# design.net
KiCad netlist of a schematic drawn in Altium Designer
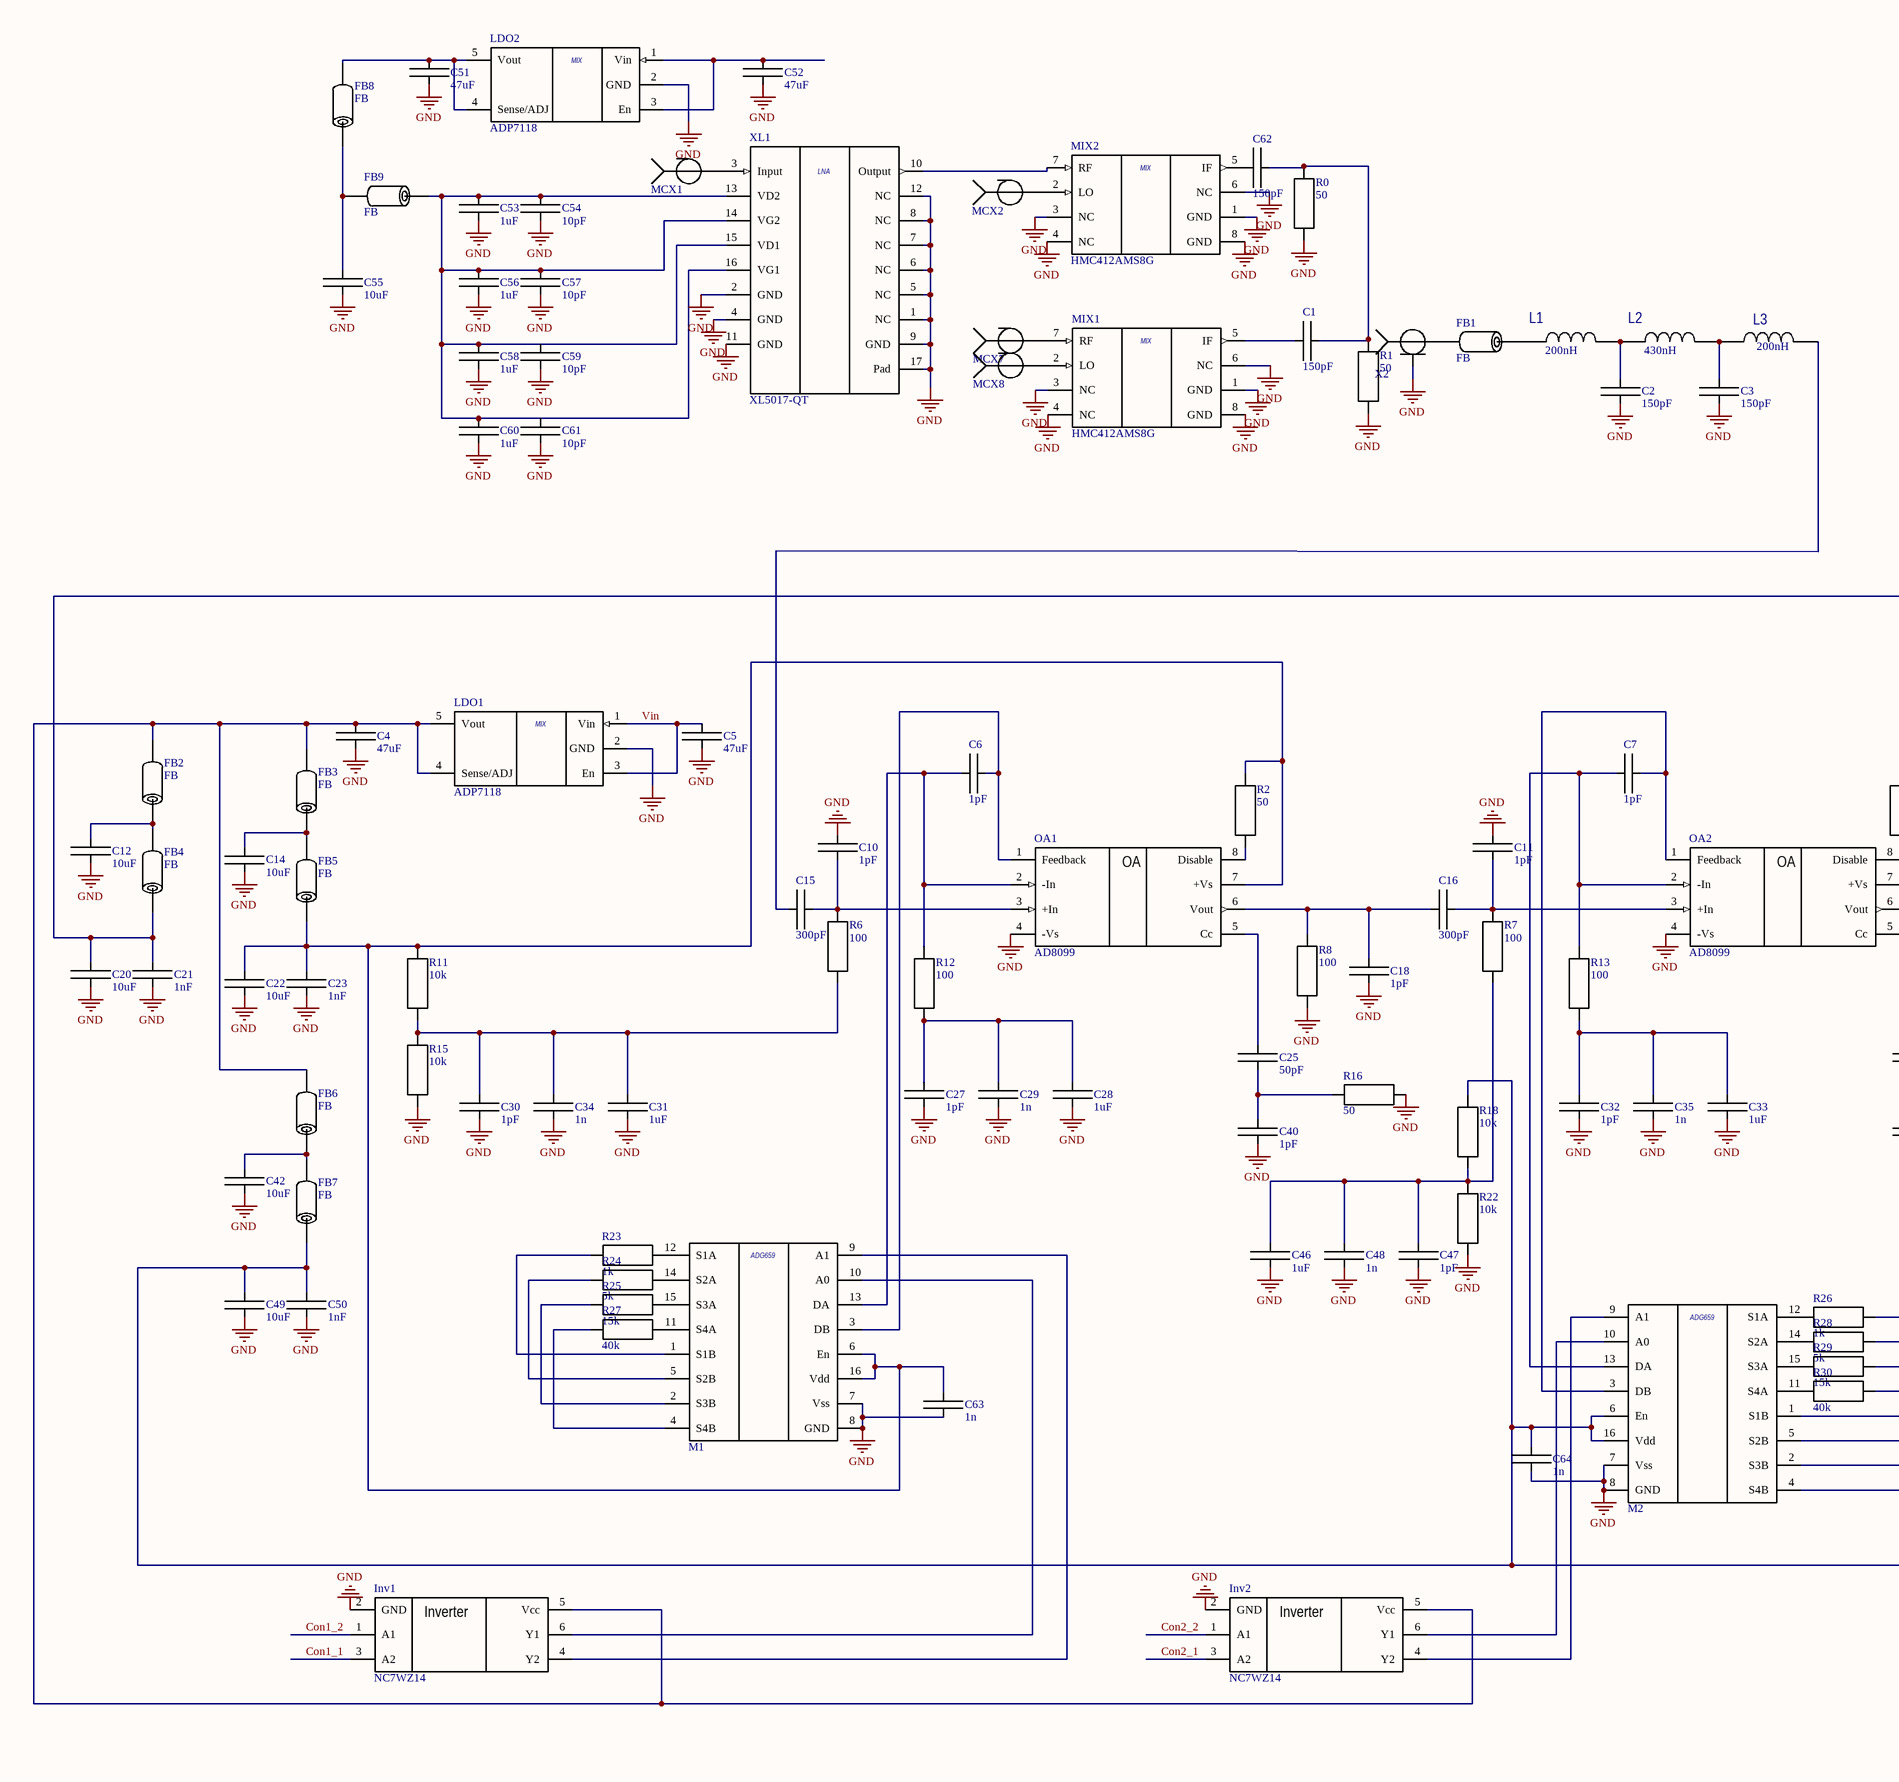
[diagram p0: Приемник.SchDoc, left]
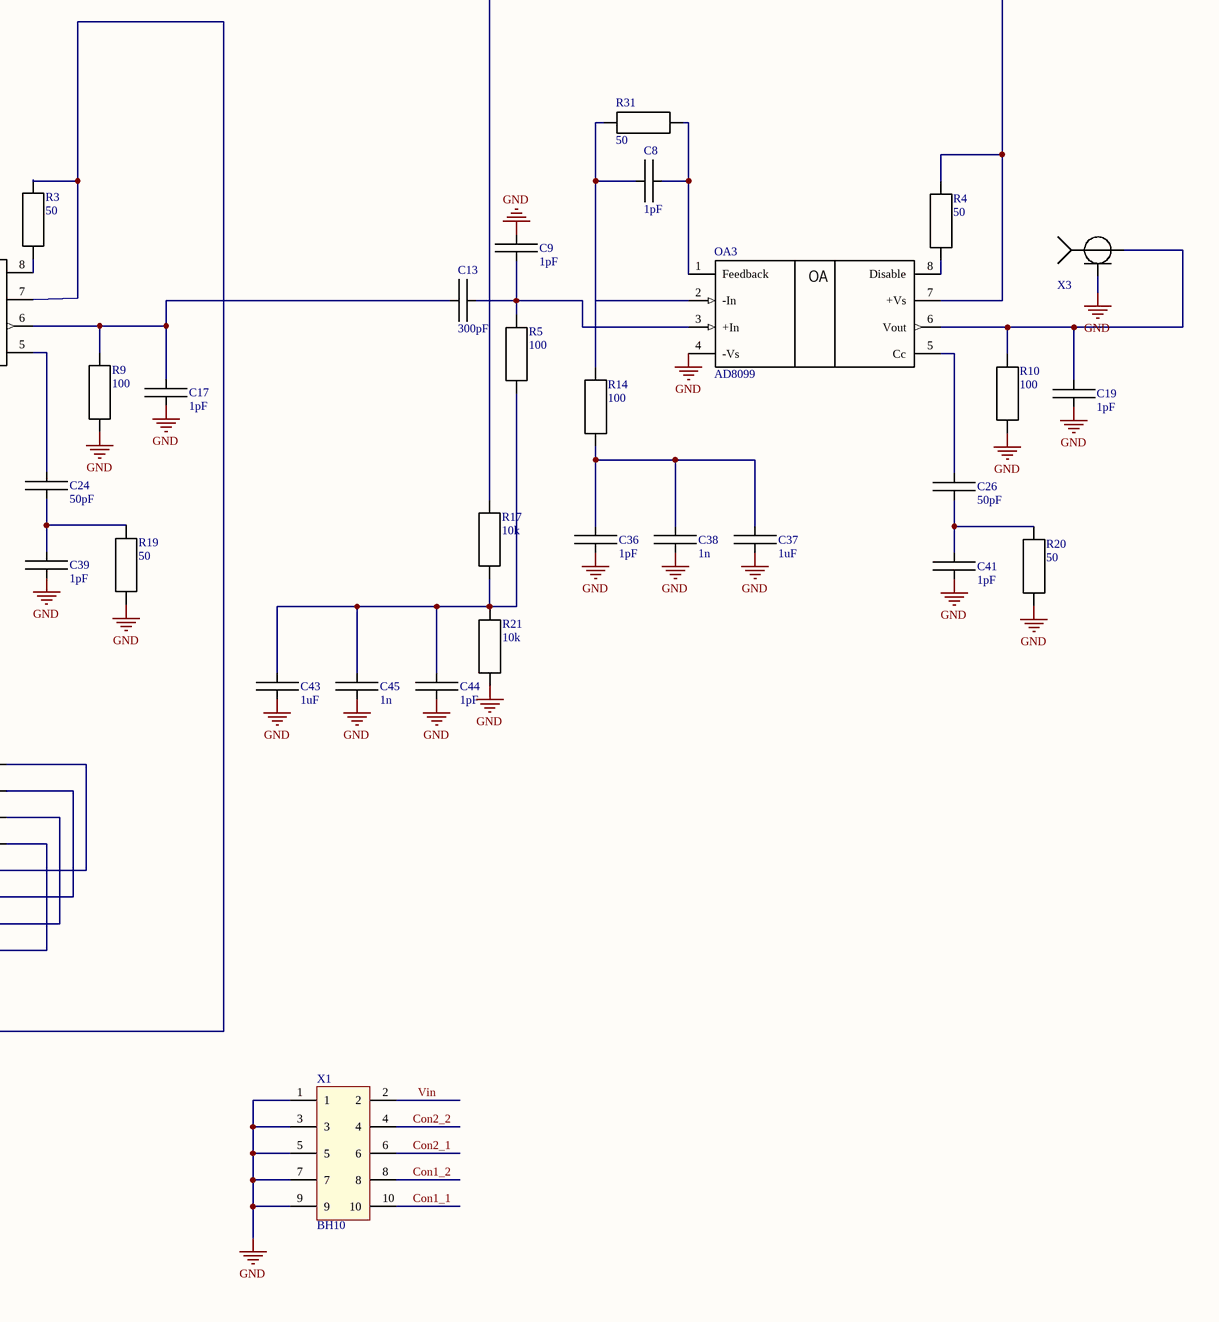
[diagram p1: Приемник.SchDoc, right]

(export (version "E")
  (design (tool "Eeschema 10.0.6"))
  (components
    (comp (ref "C1") (value "150pF") (footprint "SMD0402") (libsource (lib "My_Library") (part "CAP0402")))
    (comp (ref "C2") (value "150pF") (footprint "SMD0402") (libsource (lib "My_Library") (part "CAP0402")))
    (comp (ref "C3") (value "150pF") (footprint "SMD0402") (libsource (lib "My_Library") (part "CAP0402")))
    (comp (ref "C4")
      (value "47uF")
      (footprint "B3528-21")
      (libsource (lib "My_Library") (part "CAPT10V4.7-100uF"))
    )
    (comp (ref "C5")
      (value "47uF")
      (footprint "B3528-21")
      (libsource (lib "My_Library") (part "CAPT10V4.7-100uF"))
    )
    (comp (ref "C6") (value "1pF") (footprint "SMD0402") (libsource (lib "My_Library") (part "CAP0402")))
    (comp (ref "C7") (value "1pF") (footprint "SMD0402") (libsource (lib "My_Library") (part "CAP0402")))
    (comp (ref "C8") (value "1pF") (footprint "SMD0402") (libsource (lib "My_Library") (part "CAP0402")))
    (comp (ref "C9") (value "1pF") (footprint "SMD0402") (libsource (lib "My_Library") (part "CAP0402")))
    (comp (ref "C10") (value "1pF") (footprint "SMD0402") (libsource (lib "My_Library") (part "CAP0402")))
    (comp (ref "C11") (value "1pF") (footprint "SMD0402") (libsource (lib "My_Library") (part "CAP0402")))
    (comp (ref "C12") (value "10uF") (footprint "SMD0603") (libsource (lib "My_Library") (part "CAP0603")))
    (comp (ref "C13") (value "300pF") (footprint "SMD0402") (libsource (lib "My_Library") (part "CAP0402")))
    (comp (ref "C14") (value "10uF") (footprint "SMD0603") (libsource (lib "My_Library") (part "CAP0603")))
    (comp (ref "C15") (value "300pF") (footprint "SMD0402") (libsource (lib "My_Library") (part "CAP0402")))
    (comp (ref "C16") (value "300pF") (footprint "SMD0402") (libsource (lib "My_Library") (part "CAP0402")))
    (comp (ref "C17") (value "1pF") (footprint "SMD0402") (libsource (lib "My_Library") (part "CAP0402")))
    (comp (ref "C18") (value "1pF") (footprint "SMD0402") (libsource (lib "My_Library") (part "CAP0402")))
    (comp (ref "C19") (value "1pF") (footprint "SMD0402") (libsource (lib "My_Library") (part "CAP0402")))
    (comp (ref "C20") (value "10uF") (footprint "SMD0603") (libsource (lib "My_Library") (part "CAP0603")))
    (comp (ref "C21") (value "1nF") (footprint "SMD0402") (libsource (lib "My_Library") (part "CAP0402")))
    (comp (ref "C22") (value "10uF") (footprint "SMD0603") (libsource (lib "My_Library") (part "CAP0603")))
    (comp (ref "C23") (value "1nF") (footprint "SMD0402") (libsource (lib "My_Library") (part "CAP0402")))
    (comp (ref "C24") (value "50pF") (footprint "SMD0402") (libsource (lib "My_Library") (part "CAP0402")))
    (comp (ref "C25") (value "50pF") (footprint "SMD0402") (libsource (lib "My_Library") (part "CAP0402")))
    (comp (ref "C26") (value "50pF") (footprint "SMD0402") (libsource (lib "My_Library") (part "CAP0402")))
    (comp (ref "C27") (value "1pF") (footprint "SMD0402") (libsource (lib "My_Library") (part "CAP0402")))
    (comp (ref "C28") (value "1uF") (footprint "SMD0603") (libsource (lib "My_Library") (part "CAP0603")))
    (comp (ref "C29") (value "1n") (footprint "SMD0402") (libsource (lib "My_Library") (part "CAP0402")))
    (comp (ref "C30") (value "1pF") (footprint "SMD0402") (libsource (lib "My_Library") (part "CAP0402")))
    (comp (ref "C31") (value "1uF") (footprint "SMD0603") (libsource (lib "My_Library") (part "CAP0603")))
    (comp (ref "C32") (value "1pF") (footprint "SMD0402") (libsource (lib "My_Library") (part "CAP0402")))
    (comp (ref "C33") (value "1uF") (footprint "SMD0603") (libsource (lib "My_Library") (part "CAP0603")))
    (comp (ref "C34") (value "1n") (footprint "SMD0402") (libsource (lib "My_Library") (part "CAP0402")))
    (comp (ref "C35") (value "1n") (footprint "SMD0402") (libsource (lib "My_Library") (part "CAP0402")))
    (comp (ref "C36") (value "1pF") (footprint "SMD0402") (libsource (lib "My_Library") (part "CAP0402")))
    (comp (ref "C37") (value "1uF") (footprint "SMD0603") (libsource (lib "My_Library") (part "CAP0603")))
    (comp (ref "C38") (value "1n") (footprint "SMD0402") (libsource (lib "My_Library") (part "CAP0402")))
    (comp (ref "C39") (value "1pF") (footprint "SMD0402") (libsource (lib "My_Library") (part "CAP0402")))
    (comp (ref "C40") (value "1pF") (footprint "SMD0402") (libsource (lib "My_Library") (part "CAP0402")))
    (comp (ref "C41") (value "1pF") (footprint "SMD0402") (libsource (lib "My_Library") (part "CAP0402")))
    (comp (ref "C42") (value "10uF") (footprint "SMD0603") (libsource (lib "My_Library") (part "CAP0603")))
    (comp (ref "C43") (value "1uF") (footprint "SMD0603") (libsource (lib "My_Library") (part "CAP0603")))
    (comp (ref "C44") (value "1pF") (footprint "SMD0402") (libsource (lib "My_Library") (part "CAP0402")))
    (comp (ref "C45") (value "1n") (footprint "SMD0402") (libsource (lib "My_Library") (part "CAP0402")))
    (comp (ref "C46") (value "1uF") (footprint "SMD0603") (libsource (lib "My_Library") (part "CAP0603")))
    (comp (ref "C47") (value "1pF") (footprint "SMD0402") (libsource (lib "My_Library") (part "CAP0402")))
    (comp (ref "C48") (value "1n") (footprint "SMD0402") (libsource (lib "My_Library") (part "CAP0402")))
    (comp (ref "C49") (value "10uF") (footprint "SMD0603") (libsource (lib "My_Library") (part "CAP0603")))
    (comp (ref "C50") (value "1nF") (footprint "SMD0402") (libsource (lib "My_Library") (part "CAP0402")))
    (comp (ref "C51")
      (value "47uF")
      (footprint "B3528-21")
      (libsource (lib "My_Library") (part "CAPT10V4.7-100uF"))
    )
    (comp (ref "C52")
      (value "47uF")
      (footprint "B3528-21")
      (libsource (lib "My_Library") (part "CAPT10V4.7-100uF"))
    )
    (comp (ref "C53") (value "1uF") (footprint "SMD0603") (libsource (lib "My_Library") (part "CAP0603")))
    (comp (ref "C54") (value "10pF") (footprint "SMD0402") (libsource (lib "My_Library") (part "CAP0402")))
    (comp (ref "C55") (value "10uF") (footprint "SMD0603") (libsource (lib "My_Library") (part "CAP0603")))
    (comp (ref "C56") (value "1uF") (footprint "SMD0603") (libsource (lib "My_Library") (part "CAP0603")))
    (comp (ref "C57") (value "10pF") (footprint "SMD0402") (libsource (lib "My_Library") (part "CAP0402")))
    (comp (ref "C58") (value "1uF") (footprint "SMD0603") (libsource (lib "My_Library") (part "CAP0603")))
    (comp (ref "C59") (value "10pF") (footprint "SMD0402") (libsource (lib "My_Library") (part "CAP0402")))
    (comp (ref "C60") (value "1uF") (footprint "SMD0603") (libsource (lib "My_Library") (part "CAP0603")))
    (comp (ref "C61") (value "10pF") (footprint "SMD0402") (libsource (lib "My_Library") (part "CAP0402")))
    (comp (ref "C62") (value "150pF") (footprint "SMD0402") (libsource (lib "My_Library") (part "CAP0402")))
    (comp (ref "C63") (value "1n") (footprint "SMD0402") (libsource (lib "My_Library") (part "CAP0402")))
    (comp (ref "C64") (value "1n") (footprint "SMD0402") (libsource (lib "My_Library") (part "CAP0402")))
    (comp (ref "FB1") (value "FB") (footprint "FV1206") (libsource (lib "") (part "FB_1")))
    (comp (ref "FB2") (value "FB") (footprint "FV1206") (libsource (lib "My_Library") (part "FB")))
    (comp (ref "FB3") (value "FB") (footprint "FV1206") (libsource (lib "My_Library") (part "FB")))
    (comp (ref "FB4") (value "FB") (footprint "FV1206") (libsource (lib "My_Library") (part "FB")))
    (comp (ref "FB5") (value "FB") (footprint "FV1206") (libsource (lib "My_Library") (part "FB")))
    (comp (ref "FB6") (value "FB") (footprint "FV1206") (libsource (lib "My_Library") (part "FB")))
    (comp (ref "FB7") (value "FB") (footprint "FV1206") (libsource (lib "My_Library") (part "FB")))
    (comp (ref "FB8") (value "FB") (footprint "FV1206") (libsource (lib "My_Library") (part "FB")))
    (comp (ref "FB9") (value "FB") (footprint "FV1206") (libsource (lib "") (part "FB_1")))
    (comp (ref "Inv1") (value "NC7WZ14") (footprint "SC70") (libsource (lib "My_Library") (part "NC7WZ14")))
    (comp (ref "Inv2") (value "NC7WZ14") (footprint "SC70") (libsource (lib "My_Library") (part "NC7WZ14")))
    (comp (ref "L1") (value "200nH") (footprint "SMD0603") (libsource (lib "My_Library") (part "IND0603")))
    (comp (ref "L2") (value "430nH") (footprint "SMD0603") (libsource (lib "My_Library") (part "IND0603")))
    (comp (ref "L3") (value "200nH") (footprint "SMD0603") (libsource (lib "My_Library") (part "IND0603")))
    (comp (ref "LDO1") (value "ADP7118") (footprint "TSOT5") (libsource (lib "My_Library") (part "ADP7118")))
    (comp (ref "LDO2") (value "ADP7118") (footprint "TSOT5") (libsource (lib "My_Library") (part "ADP7118")))
    (comp (ref "M1")
      (value "ADG658_659")
      (footprint "TSSOP16")
      (libsource (lib "My_Library") (part "ADG658_659"))
    )
    (comp (ref "M2")
      (value "ADG658_659")
      (footprint "TSSOP16")
      (libsource (lib "My_Library") (part "ADG658_659"))
    )
    (comp (ref "MCX1") (value "MCX") (footprint "MCX") (libsource (lib "My_Library") (part "MCX")))
    (comp (ref "MCX2") (value "MCX") (footprint "MCX") (libsource (lib "My_Library") (part "MCX")))
    (comp (ref "MCX7") (value "MCX") (footprint "MCX") (libsource (lib "My_Library") (part "MCX")))
    (comp (ref "MCX8") (value "MCX") (footprint "MCX") (libsource (lib "My_Library") (part "MCX")))
    (comp (ref "MIX1")
      (value "HMC412AMS8G")
      (footprint "HMC412AMS8G")
      (libsource (lib "My_Library") (part "HMC412AMS8G"))
    )
    (comp (ref "MIX2")
      (value "HMC412AMS8G")
      (footprint "HMC412AMS8G")
      (libsource (lib "My_Library") (part "HMC412AMS8G"))
    )
    (comp (ref "OA1") (value "AD8099") (footprint "SOIC_8_EP") (libsource (lib "My_Library") (part "AD8099")))
    (comp (ref "OA2") (value "AD8099") (footprint "SOIC_8_EP") (libsource (lib "My_Library") (part "AD8099")))
    (comp (ref "OA3") (value "AD8099") (footprint "SOIC_8_EP") (libsource (lib "My_Library") (part "AD8099")))
    (comp (ref "R0") (value "50") (footprint "SMD0603") (libsource (lib "My_Library") (part "RES0402")))
    (comp (ref "R1") (value "50") (footprint "SMD0603") (libsource (lib "My_Library") (part "RES0402")))
    (comp (ref "R2") (value "50") (footprint "SMD0603") (libsource (lib "My_Library") (part "RES0402")))
    (comp (ref "R3") (value "50") (footprint "SMD0603") (libsource (lib "My_Library") (part "RES0402")))
    (comp (ref "R4") (value "50") (footprint "SMD0603") (libsource (lib "My_Library") (part "RES0402")))
    (comp (ref "R5") (value "100") (footprint "SMD0603") (libsource (lib "My_Library") (part "RES0402")))
    (comp (ref "R6") (value "100") (footprint "SMD0603") (libsource (lib "My_Library") (part "RES0402")))
    (comp (ref "R7") (value "100") (footprint "SMD0603") (libsource (lib "My_Library") (part "RES0402")))
    (comp (ref "R8") (value "100") (footprint "SMD0603") (libsource (lib "My_Library") (part "RES0402")))
    (comp (ref "R9") (value "100") (footprint "SMD0603") (libsource (lib "My_Library") (part "RES0402")))
    (comp (ref "R10") (value "100") (footprint "SMD0603") (libsource (lib "My_Library") (part "RES0402")))
    (comp (ref "R11") (value "10k") (footprint "SMD0603") (libsource (lib "My_Library") (part "RES0402")))
    (comp (ref "R12") (value "100") (footprint "SMD0603") (libsource (lib "My_Library") (part "RES0402")))
    (comp (ref "R13") (value "100") (footprint "SMD0603") (libsource (lib "My_Library") (part "RES0402")))
    (comp (ref "R14") (value "100") (footprint "SMD0603") (libsource (lib "My_Library") (part "RES0402")))
    (comp (ref "R15") (value "10k") (footprint "SMD0603") (libsource (lib "My_Library") (part "RES0402")))
    (comp (ref "R16") (value "50") (footprint "SMD0603") (libsource (lib "My_Library") (part "RES0402")))
    (comp (ref "R17") (value "10k") (footprint "SMD0603") (libsource (lib "My_Library") (part "RES0402")))
    (comp (ref "R18") (value "10k") (footprint "SMD0603") (libsource (lib "My_Library") (part "RES0402")))
    (comp (ref "R19") (value "50") (footprint "SMD0603") (libsource (lib "My_Library") (part "RES0402")))
    (comp (ref "R20") (value "50") (footprint "SMD0603") (libsource (lib "My_Library") (part "RES0402")))
    (comp (ref "R21") (value "10k") (footprint "SMD0603") (libsource (lib "My_Library") (part "RES0402")))
    (comp (ref "R22") (value "10k") (footprint "SMD0603") (libsource (lib "My_Library") (part "RES0402")))
    (comp (ref "R23") (value "1k") (footprint "SMD0603") (libsource (lib "My_Library") (part "RES0402")))
    (comp (ref "R24") (value "5k") (footprint "SMD0603") (libsource (lib "My_Library") (part "RES0402")))
    (comp (ref "R25") (value "15k") (footprint "SMD0603") (libsource (lib "My_Library") (part "RES0402")))
    (comp (ref "R26") (value "1k") (footprint "SMD0603") (libsource (lib "My_Library") (part "RES0402")))
    (comp (ref "R27") (value "40k") (footprint "SMD0603") (libsource (lib "My_Library") (part "RES0402")))
    (comp (ref "R28") (value "5k") (footprint "SMD0603") (libsource (lib "My_Library") (part "RES0402")))
    (comp (ref "R29") (value "15k") (footprint "SMD0603") (libsource (lib "My_Library") (part "RES0402")))
    (comp (ref "R30") (value "40k") (footprint "SMD0603") (libsource (lib "My_Library") (part "RES0402")))
    (comp (ref "R31") (value "50") (footprint "SMD0603") (libsource (lib "My_Library") (part "RES0402")))
    (comp (ref "X1") (value "BH10") (footprint "BH10") (libsource (lib "Integrated_Library") (part "BH10")))
    (comp (ref "X2")
      (value "MCX 1085221-1")
      (footprint "MCX")
      (libsource (lib "Integrated_Library") (part "MCX 1085221-1"))
    )
    (comp (ref "X3")
      (value "MCX 1085221-1")
      (footprint "MCX")
      (libsource (lib "Integrated_Library") (part "MCX 1085221-1"))
    )
    (comp (ref "XL1")
      (value "XL5017-QT")
      (footprint "XL5017-QT")
      (libsource (lib "My_Library") (part "XL5017-QT"))
    )
  )
  (nets
    (net (code "1") (name "/Con1_1") (class "Default")
      (node (ref "Inv1") (pin "3") (pinfunction "A2_3") (pintype "passive"))
      (node (ref "X1") (pin "10") (pinfunction "10_10") (pintype "passive"))
    )
    (net (code "2") (name "/Con1_2") (class "Default")
      (node (ref "Inv1") (pin "1") (pinfunction "A1_1") (pintype "passive"))
      (node (ref "X1") (pin "8") (pinfunction "8_8") (pintype "passive"))
    )
    (net (code "3") (name "/Con2_1") (class "Default")
      (node (ref "Inv2") (pin "3") (pinfunction "A2_3") (pintype "passive"))
      (node (ref "X1") (pin "6") (pinfunction "6_6") (pintype "passive"))
    )
    (net (code "4") (name "/Con2_2") (class "Default")
      (node (ref "Inv2") (pin "1") (pinfunction "A1_1") (pintype "passive"))
      (node (ref "X1") (pin "4") (pinfunction "4_4") (pintype "passive"))
    )
    (net (code "5") (name "/Vin") (class "Default")
      (node (ref "C5") (pin "2") (pinfunction "2_2") (pintype "passive"))
      (node (ref "LDO1") (pin "1") (pinfunction "Vin_1") (pintype "input"))
      (node (ref "LDO1") (pin "3") (pinfunction "En_3") (pintype "passive"))
      (node (ref "X1") (pin "2") (pinfunction "2_2") (pintype "passive"))
    )
    (net (code "6") (name "GND") (class "Default")
      (node (ref "C10") (pin "2") (pinfunction "2_2") (pintype "passive"))
      (node (ref "C11") (pin "1") (pinfunction "1_1") (pintype "passive"))
      (node (ref "C12") (pin "1") (pinfunction "1_1") (pintype "passive"))
      (node (ref "C14") (pin "1") (pinfunction "1_1") (pintype "passive"))
      (node (ref "C17") (pin "1") (pinfunction "1_1") (pintype "passive"))
      (node (ref "C18") (pin "2") (pinfunction "2_2") (pintype "passive"))
      (node (ref "C19") (pin "1") (pinfunction "1_1") (pintype "passive"))
      (node (ref "C2") (pin "1") (pinfunction "1_1") (pintype "passive"))
      (node (ref "C20") (pin "1") (pinfunction "1_1") (pintype "passive"))
      (node (ref "C21") (pin "2") (pinfunction "2_2") (pintype "passive"))
      (node (ref "C22") (pin "1") (pinfunction "1_1") (pintype "passive"))
      (node (ref "C23") (pin "2") (pinfunction "2_2") (pintype "passive"))
      (node (ref "C27") (pin "1") (pinfunction "1_1") (pintype "passive"))
      (node (ref "C28") (pin "1") (pinfunction "1_1") (pintype "passive"))
      (node (ref "C29") (pin "1") (pinfunction "1_1") (pintype "passive"))
      (node (ref "C3") (pin "1") (pinfunction "1_1") (pintype "passive"))
      (node (ref "C30") (pin "1") (pinfunction "1_1") (pintype "passive"))
      (node (ref "C31") (pin "1") (pinfunction "1_1") (pintype "passive"))
      (node (ref "C32") (pin "1") (pinfunction "1_1") (pintype "passive"))
      (node (ref "C33") (pin "1") (pinfunction "1_1") (pintype "passive"))
      (node (ref "C34") (pin "1") (pinfunction "1_1") (pintype "passive"))
      (node (ref "C35") (pin "1") (pinfunction "1_1") (pintype "passive"))
      (node (ref "C36") (pin "1") (pinfunction "1_1") (pintype "passive"))
      (node (ref "C37") (pin "1") (pinfunction "1_1") (pintype "passive"))
      (node (ref "C38") (pin "1") (pinfunction "1_1") (pintype "passive"))
      (node (ref "C39") (pin "1") (pinfunction "1_1") (pintype "passive"))
      (node (ref "C4") (pin "1") (pinfunction "1_1") (pintype "passive"))
      (node (ref "C40") (pin "2") (pinfunction "2_2") (pintype "passive"))
      (node (ref "C41") (pin "1") (pinfunction "1_1") (pintype "passive"))
      (node (ref "C42") (pin "1") (pinfunction "1_1") (pintype "passive"))
      (node (ref "C43") (pin "1") (pinfunction "1_1") (pintype "passive"))
      (node (ref "C44") (pin "1") (pinfunction "1_1") (pintype "passive"))
      (node (ref "C45") (pin "1") (pinfunction "1_1") (pintype "passive"))
      (node (ref "C46") (pin "1") (pinfunction "1_1") (pintype "passive"))
      (node (ref "C47") (pin "1") (pinfunction "1_1") (pintype "passive"))
      (node (ref "C48") (pin "1") (pinfunction "1_1") (pintype "passive"))
      (node (ref "C49") (pin "1") (pinfunction "1_1") (pintype "passive"))
      (node (ref "C5") (pin "1") (pinfunction "1_1") (pintype "passive"))
      (node (ref "C50") (pin "2") (pinfunction "2_2") (pintype "passive"))
      (node (ref "C51") (pin "1") (pinfunction "1_1") (pintype "passive"))
      (node (ref "C52") (pin "1") (pinfunction "1_1") (pintype "passive"))
      (node (ref "C53") (pin "1") (pinfunction "1_1") (pintype "passive"))
      (node (ref "C54") (pin "1") (pinfunction "1_1") (pintype "passive"))
      (node (ref "C55") (pin "1") (pinfunction "1_1") (pintype "passive"))
      (node (ref "C56") (pin "1") (pinfunction "1_1") (pintype "passive"))
      (node (ref "C57") (pin "1") (pinfunction "1_1") (pintype "passive"))
      (node (ref "C58") (pin "1") (pinfunction "1_1") (pintype "passive"))
      (node (ref "C59") (pin "1") (pinfunction "1_1") (pintype "passive"))
      (node (ref "C60") (pin "1") (pinfunction "1_1") (pintype "passive"))
      (node (ref "C61") (pin "1") (pinfunction "1_1") (pintype "passive"))
      (node (ref "C63") (pin "1") (pinfunction "1_1") (pintype "passive"))
      (node (ref "C64") (pin "1") (pinfunction "1_1") (pintype "passive"))
      (node (ref "C9") (pin "1") (pinfunction "1_1") (pintype "passive"))
      (node (ref "Inv1") (pin "2") (pinfunction "GND_2") (pintype "passive"))
      (node (ref "Inv2") (pin "2") (pinfunction "GND_2") (pintype "passive"))
      (node (ref "LDO1") (pin "2") (pinfunction "GND_2") (pintype "passive"))
      (node (ref "LDO2") (pin "2") (pinfunction "GND_2") (pintype "passive"))
      (node (ref "M1") (pin "7") (pinfunction "Vss_7") (pintype "passive"))
      (node (ref "M1") (pin "8") (pinfunction "GND_8") (pintype "passive"))
      (node (ref "M2") (pin "7") (pinfunction "Vss_7") (pintype "passive"))
      (node (ref "M2") (pin "8") (pinfunction "GND_8") (pintype "passive"))
      (node (ref "MIX1") (pin "1") (pinfunction "GND_1") (pintype "passive"))
      (node (ref "MIX1") (pin "3") (pinfunction "NC_3") (pintype "passive"))
      (node (ref "MIX1") (pin "4") (pinfunction "NC_4") (pintype "passive"))
      (node (ref "MIX1") (pin "6") (pinfunction "NC_6") (pintype "passive"))
      (node (ref "MIX1") (pin "8") (pinfunction "GND_8") (pintype "passive"))
      (node (ref "MIX2") (pin "1") (pinfunction "GND_1") (pintype "passive"))
      (node (ref "MIX2") (pin "3") (pinfunction "NC_3") (pintype "passive"))
      (node (ref "MIX2") (pin "4") (pinfunction "NC_4") (pintype "passive"))
      (node (ref "MIX2") (pin "6") (pinfunction "NC_6") (pintype "passive"))
      (node (ref "MIX2") (pin "8") (pinfunction "GND_8") (pintype "passive"))
      (node (ref "OA1") (pin "4") (pinfunction "-Vs_4") (pintype "passive"))
      (node (ref "OA2") (pin "4") (pinfunction "-Vs_4") (pintype "passive"))
      (node (ref "OA3") (pin "4") (pinfunction "-Vs_4") (pintype "passive"))
      (node (ref "R0") (pin "1") (pinfunction "1_1") (pintype "passive"))
      (node (ref "R1") (pin "1") (pinfunction "1_1") (pintype "passive"))
      (node (ref "R10") (pin "2") (pinfunction "2_2") (pintype "passive"))
      (node (ref "R15") (pin "1") (pinfunction "1_1") (pintype "passive"))
      (node (ref "R16") (pin "2") (pinfunction "2_2") (pintype "passive"))
      (node (ref "R19") (pin "2") (pinfunction "2_2") (pintype "passive"))
      (node (ref "R20") (pin "2") (pinfunction "2_2") (pintype "passive"))
      (node (ref "R21") (pin "1") (pinfunction "1_1") (pintype "passive"))
      (node (ref "R22") (pin "1") (pinfunction "1_1") (pintype "passive"))
      (node (ref "R8") (pin "2") (pinfunction "2_2") (pintype "passive"))
      (node (ref "R9") (pin "2") (pinfunction "2_2") (pintype "passive"))
      (node (ref "X1") (pin "1") (pinfunction "1_1") (pintype "passive"))
      (node (ref "X1") (pin "3") (pinfunction "3_3") (pintype "passive"))
      (node (ref "X1") (pin "5") (pinfunction "5_5") (pintype "passive"))
      (node (ref "X1") (pin "7") (pinfunction "7_7") (pintype "passive"))
      (node (ref "X1") (pin "9") (pinfunction "9_9") (pintype "passive"))
      (node (ref "X2") (pin "2") (pinfunction "2_2") (pintype "passive"))
      (node (ref "X3") (pin "2") (pinfunction "2_2") (pintype "passive"))
      (node (ref "XL1") (pin "1") (pinfunction "NC_1") (pintype "passive"))
      (node (ref "XL1") (pin "11") (pinfunction "GND_11") (pintype "passive"))
      (node (ref "XL1") (pin "12") (pinfunction "NC_12") (pintype "passive"))
      (node (ref "XL1") (pin "17") (pinfunction "Pad_17") (pintype "passive"))
      (node (ref "XL1") (pin "2") (pinfunction "GND_2") (pintype "passive"))
      (node (ref "XL1") (pin "4") (pinfunction "GND_4") (pintype "passive"))
      (node (ref "XL1") (pin "5") (pinfunction "NC_5") (pintype "passive"))
      (node (ref "XL1") (pin "6") (pinfunction "NC_6") (pintype "passive"))
      (node (ref "XL1") (pin "7") (pinfunction "NC_7") (pintype "passive"))
      (node (ref "XL1") (pin "8") (pinfunction "NC_8") (pintype "passive"))
      (node (ref "XL1") (pin "9") (pinfunction "GND_9") (pintype "passive"))
    )
    (net (code "7") (name "Net-(C1-Pad1)") (class "Default")
      (node (ref "C1") (pin "1") (pinfunction "1_1") (pintype "passive"))
      (node (ref "C62") (pin "2") (pinfunction "2_2") (pintype "passive"))
      (node (ref "R0") (pin "2") (pinfunction "2_2") (pintype "passive"))
      (node (ref "R1") (pin "2") (pinfunction "2_2") (pintype "passive"))
    )
    (net (code "8") (name "Net-(C12-Pad2)") (class "Default")
      (node (ref "C12") (pin "2") (pinfunction "2_2") (pintype "passive"))
      (node (ref "FB2") (pin "1") (pinfunction "1_1") (pintype "passive"))
      (node (ref "FB4") (pin "2") (pinfunction "2_2") (pintype "passive"))
    )
    (net (code "9") (name "Net-(C14-Pad2)") (class "Default")
      (node (ref "C14") (pin "2") (pinfunction "2_2") (pintype "passive"))
      (node (ref "FB3") (pin "1") (pinfunction "1_1") (pintype "passive"))
      (node (ref "FB5") (pin "2") (pinfunction "2_2") (pintype "passive"))
    )
    (net (code "10") (name "Net-(C24-Pad1)") (class "Default")
      (node (ref "C24") (pin "1") (pinfunction "1_1") (pintype "passive"))
      (node (ref "C39") (pin "2") (pinfunction "2_2") (pintype "passive"))
      (node (ref "R19") (pin "1") (pinfunction "1_1") (pintype "passive"))
    )
    (net (code "11") (name "Net-(C25-Pad2)") (class "Default")
      (node (ref "C25") (pin "2") (pinfunction "2_2") (pintype "passive"))
      (node (ref "C40") (pin "1") (pinfunction "1_1") (pintype "passive"))
      (node (ref "R16") (pin "1") (pinfunction "1_1") (pintype "passive"))
    )
    (net (code "12") (name "Net-(C26-Pad1)") (class "Default")
      (node (ref "C26") (pin "1") (pinfunction "1_1") (pintype "passive"))
      (node (ref "C41") (pin "2") (pinfunction "2_2") (pintype "passive"))
      (node (ref "R20") (pin "1") (pinfunction "1_1") (pintype "passive"))
    )
    (net (code "13") (name "Net-(C27-Pad2)") (class "Default")
      (node (ref "C27") (pin "2") (pinfunction "2_2") (pintype "passive"))
      (node (ref "C28") (pin "2") (pinfunction "2_2") (pintype "passive"))
      (node (ref "C29") (pin "2") (pinfunction "2_2") (pintype "passive"))
      (node (ref "R12") (pin "1") (pinfunction "1_1") (pintype "passive"))
    )
    (net (code "14") (name "Net-(C30-Pad2)") (class "Default")
      (node (ref "C30") (pin "2") (pinfunction "2_2") (pintype "passive"))
      (node (ref "C31") (pin "2") (pinfunction "2_2") (pintype "passive"))
      (node (ref "C34") (pin "2") (pinfunction "2_2") (pintype "passive"))
      (node (ref "R11") (pin "1") (pinfunction "1_1") (pintype "passive"))
      (node (ref "R15") (pin "2") (pinfunction "2_2") (pintype "passive"))
      (node (ref "R6") (pin "1") (pinfunction "1_1") (pintype "passive"))
    )
    (net (code "15") (name "Net-(C32-Pad2)") (class "Default")
      (node (ref "C32") (pin "2") (pinfunction "2_2") (pintype "passive"))
      (node (ref "C33") (pin "2") (pinfunction "2_2") (pintype "passive"))
      (node (ref "C35") (pin "2") (pinfunction "2_2") (pintype "passive"))
      (node (ref "R13") (pin "1") (pinfunction "1_1") (pintype "passive"))
    )
    (net (code "16") (name "Net-(C36-Pad2)") (class "Default")
      (node (ref "C36") (pin "2") (pinfunction "2_2") (pintype "passive"))
      (node (ref "C37") (pin "2") (pinfunction "2_2") (pintype "passive"))
      (node (ref "C38") (pin "2") (pinfunction "2_2") (pintype "passive"))
      (node (ref "R14") (pin "1") (pinfunction "1_1") (pintype "passive"))
    )
    (net (code "17") (name "Net-(C42-Pad2)") (class "Default")
      (node (ref "C42") (pin "2") (pinfunction "2_2") (pintype "passive"))
      (node (ref "FB6") (pin "1") (pinfunction "1_1") (pintype "passive"))
      (node (ref "FB7") (pin "2") (pinfunction "2_2") (pintype "passive"))
    )
    (net (code "18") (name "Net-(C43-Pad2)") (class "Default")
      (node (ref "C43") (pin "2") (pinfunction "2_2") (pintype "passive"))
      (node (ref "C44") (pin "2") (pinfunction "2_2") (pintype "passive"))
      (node (ref "C45") (pin "2") (pinfunction "2_2") (pintype "passive"))
      (node (ref "R17") (pin "1") (pinfunction "1_1") (pintype "passive"))
      (node (ref "R21") (pin "2") (pinfunction "2_2") (pintype "passive"))
      (node (ref "R5") (pin "1") (pinfunction "1_1") (pintype "passive"))
    )
    (net (code "19") (name "Net-(C46-Pad2)") (class "Default")
      (node (ref "C46") (pin "2") (pinfunction "2_2") (pintype "passive"))
      (node (ref "C47") (pin "2") (pinfunction "2_2") (pintype "passive"))
      (node (ref "C48") (pin "2") (pinfunction "2_2") (pintype "passive"))
      (node (ref "R18") (pin "1") (pinfunction "1_1") (pintype "passive"))
      (node (ref "R22") (pin "2") (pinfunction "2_2") (pintype "passive"))
      (node (ref "R7") (pin "1") (pinfunction "1_1") (pintype "passive"))
    )
    (net (code "20") (name "Net-(C55-Pad2)") (class "Default")
      (node (ref "C55") (pin "2") (pinfunction "2_2") (pintype "passive"))
      (node (ref "FB8") (pin "1") (pinfunction "1_1") (pintype "passive"))
      (node (ref "FB9") (pin "2") (pinfunction "2_2") (pintype "passive"))
    )
    (net (code "21") (name "Net-(FB1-Pad1)") (class "Default")
      (node (ref "FB1") (pin "1") (pinfunction "1_1") (pintype "passive"))
      (node (ref "L1") (pin "1") (pinfunction "1_1") (pintype "passive"))
    )
    (net (code "22") (name "Net-(FB1-Pad2)") (class "Default")
      (node (ref "FB1") (pin "2") (pinfunction "2_2") (pintype "passive"))
      (node (ref "X2") (pin "1") (pinfunction "1_1") (pintype "passive"))
    )
    (net (code "23") (name "Net-(Inv1-Vcc)") (class "Default")
      (node (ref "C4") (pin "2") (pinfunction "2_2") (pintype "passive"))
      (node (ref "FB2") (pin "2") (pinfunction "2_2") (pintype "passive"))
      (node (ref "FB3") (pin "2") (pinfunction "2_2") (pintype "passive"))
      (node (ref "FB6") (pin "2") (pinfunction "2_2") (pintype "passive"))
      (node (ref "Inv1") (pin "5") (pinfunction "Vcc_5") (pintype "passive"))
      (node (ref "Inv2") (pin "5") (pinfunction "Vcc_5") (pintype "passive"))
      (node (ref "LDO1") (pin "4") (pinfunction "Sense/ADJ_4") (pintype "passive"))
      (node (ref "LDO1") (pin "5") (pinfunction "Vout_5") (pintype "passive"))
    )
    (net (code "24") (name "Net-(Inv1-Y1)") (class "Default")
      (node (ref "Inv1") (pin "6") (pinfunction "Y1_6") (pintype "passive"))
      (node (ref "M1") (pin "10") (pinfunction "A0_10") (pintype "passive"))
    )
    (net (code "25") (name "Net-(Inv1-Y2)") (class "Default")
      (node (ref "Inv1") (pin "4") (pinfunction "Y2_4") (pintype "passive"))
      (node (ref "M1") (pin "9") (pinfunction "A1_9") (pintype "passive"))
    )
    (net (code "26") (name "Net-(Inv2-Y1)") (class "Default")
      (node (ref "Inv2") (pin "6") (pinfunction "Y1_6") (pintype "passive"))
      (node (ref "M2") (pin "10") (pinfunction "A0_10") (pintype "passive"))
    )
    (net (code "27") (name "Net-(Inv2-Y2)") (class "Default")
      (node (ref "Inv2") (pin "4") (pinfunction "Y2_4") (pintype "passive"))
      (node (ref "M2") (pin "9") (pinfunction "A1_9") (pintype "passive"))
    )
    (net (code "28") (name "Net-(L1-34)") (class "Default")
      (node (ref "C2") (pin "2") (pinfunction "2_2") (pintype "passive"))
      (node (ref "L1") (pin "2") (pinfunction "34_2") (pintype "passive"))
      (node (ref "L2") (pin "1") (pinfunction "1_1") (pintype "passive"))
    )
    (net (code "29") (name "Net-(L2-34)") (class "Default")
      (node (ref "C3") (pin "2") (pinfunction "2_2") (pintype "passive"))
      (node (ref "L2") (pin "2") (pinfunction "34_2") (pintype "passive"))
      (node (ref "L3") (pin "1") (pinfunction "1_1") (pintype "passive"))
    )
    (net (code "30") (name "Net-(L3-34)") (class "Default")
      (node (ref "C15") (pin "2") (pinfunction "2_2") (pintype "passive"))
      (node (ref "L3") (pin "2") (pinfunction "34_2") (pintype "passive"))
    )
    (net (code "31") (name "Net-(LDO2-En)") (class "Default")
      (node (ref "C52") (pin "2") (pinfunction "2_2") (pintype "passive"))
      (node (ref "LDO2") (pin "1") (pinfunction "Vin_1") (pintype "input"))
      (node (ref "LDO2") (pin "3") (pinfunction "En_3") (pintype "passive"))
    )
    (net (code "32") (name "Net-(LDO2-Sense{slash}ADJ)") (class "Default")
      (node (ref "C51") (pin "2") (pinfunction "2_2") (pintype "passive"))
      (node (ref "FB8") (pin "2") (pinfunction "2_2") (pintype "passive"))
      (node (ref "LDO2") (pin "4") (pinfunction "Sense/ADJ_4") (pintype "passive"))
      (node (ref "LDO2") (pin "5") (pinfunction "Vout_5") (pintype "passive"))
    )
    (net (code "33") (name "Net-(M1-DA)") (class "Default")
      (node (ref "C6") (pin "2") (pinfunction "2_2") (pintype "passive"))
      (node (ref "M1") (pin "13") (pinfunction "DA_13") (pintype "passive"))
      (node (ref "OA1") (pin "2") (pinfunction "-In_2") (pintype "input"))
      (node (ref "R12") (pin "2") (pinfunction "2_2") (pintype "passive"))
    )
    (net (code "34") (name "Net-(M1-DB)") (class "Default")
      (node (ref "C6") (pin "1") (pinfunction "1_1") (pintype "passive"))
      (node (ref "M1") (pin "3") (pinfunction "DB_3") (pintype "passive"))
      (node (ref "OA1") (pin "1") (pinfunction "Feedback_1") (pintype "passive"))
    )
    (net (code "35") (name "Net-(M1-En)") (class "Default")
      (node (ref "C22") (pin "2") (pinfunction "2_2") (pintype "passive"))
      (node (ref "C23") (pin "1") (pinfunction "1_1") (pintype "passive"))
      (node (ref "C63") (pin "2") (pinfunction "2_2") (pintype "passive"))
      (node (ref "FB5") (pin "1") (pinfunction "1_1") (pintype "passive"))
      (node (ref "M1") (pin "16") (pinfunction "Vdd_16") (pintype "passive"))
      (node (ref "M1") (pin "6") (pinfunction "En_6") (pintype "power_in"))
      (node (ref "OA1") (pin "7") (pinfunction "+Vs_7") (pintype "passive"))
      (node (ref "R11") (pin "2") (pinfunction "2_2") (pintype "passive"))
      (node (ref "R2") (pin "1") (pinfunction "1_1") (pintype "passive"))
    )
    (net (code "36") (name "Net-(M1-S1A)") (class "Default")
      (node (ref "M1") (pin "12") (pinfunction "S1A_12") (pintype "power_in"))
      (node (ref "R23") (pin "1") (pinfunction "1_1") (pintype "passive"))
    )
    (net (code "37") (name "Net-(M1-S1B)") (class "Default")
      (node (ref "M1") (pin "1") (pinfunction "S1B_1") (pintype "power_in"))
      (node (ref "R23") (pin "2") (pinfunction "2_2") (pintype "passive"))
    )
    (net (code "38") (name "Net-(M1-S2A)") (class "Default")
      (node (ref "M1") (pin "14") (pinfunction "S2A_14") (pintype "passive"))
      (node (ref "R24") (pin "1") (pinfunction "1_1") (pintype "passive"))
    )
    (net (code "39") (name "Net-(M1-S2B)") (class "Default")
      (node (ref "M1") (pin "5") (pinfunction "S2B_5") (pintype "passive"))
      (node (ref "R24") (pin "2") (pinfunction "2_2") (pintype "passive"))
    )
    (net (code "40") (name "Net-(M1-S3A)") (class "Default")
      (node (ref "M1") (pin "15") (pinfunction "S3A_15") (pintype "passive"))
      (node (ref "R25") (pin "1") (pinfunction "1_1") (pintype "passive"))
    )
    (net (code "41") (name "Net-(M1-S3B)") (class "Default")
      (node (ref "M1") (pin "2") (pinfunction "S3B_2") (pintype "passive"))
      (node (ref "R25") (pin "2") (pinfunction "2_2") (pintype "passive"))
    )
    (net (code "42") (name "Net-(M1-S4A)") (class "Default")
      (node (ref "M1") (pin "11") (pinfunction "S4A_11") (pintype "passive"))
      (node (ref "R27") (pin "1") (pinfunction "1_1") (pintype "passive"))
    )
    (net (code "43") (name "Net-(M1-S4B)") (class "Default")
      (node (ref "M1") (pin "4") (pinfunction "S4B_4") (pintype "passive"))
      (node (ref "R27") (pin "2") (pinfunction "2_2") (pintype "passive"))
    )
    (net (code "44") (name "Net-(M2-DA)") (class "Default")
      (node (ref "C7") (pin "1") (pinfunction "1_1") (pintype "passive"))
      (node (ref "M2") (pin "13") (pinfunction "DA_13") (pintype "passive"))
      (node (ref "OA2") (pin "2") (pinfunction "-In_2") (pintype "input"))
      (node (ref "R13") (pin "2") (pinfunction "2_2") (pintype "passive"))
    )
    (net (code "45") (name "Net-(M2-DB)") (class "Default")
      (node (ref "C7") (pin "2") (pinfunction "2_2") (pintype "passive"))
      (node (ref "M2") (pin "3") (pinfunction "DB_3") (pintype "passive"))
      (node (ref "OA2") (pin "1") (pinfunction "Feedback_1") (pintype "passive"))
    )
    (net (code "46") (name "Net-(M2-En)") (class "Default")
      (node (ref "C49") (pin "2") (pinfunction "2_2") (pintype "passive"))
      (node (ref "C50") (pin "1") (pinfunction "1_1") (pintype "passive"))
      (node (ref "C64") (pin "2") (pinfunction "2_2") (pintype "passive"))
      (node (ref "FB7") (pin "1") (pinfunction "1_1") (pintype "passive"))
      (node (ref "M2") (pin "16") (pinfunction "Vdd_16") (pintype "passive"))
      (node (ref "M2") (pin "6") (pinfunction "En_6") (pintype "power_in"))
      (node (ref "OA2") (pin "7") (pinfunction "+Vs_7") (pintype "passive"))
      (node (ref "R18") (pin "2") (pinfunction "2_2") (pintype "passive"))
      (node (ref "R3") (pin "1") (pinfunction "1_1") (pintype "passive"))
    )
    (net (code "47") (name "Net-(M2-S1A)") (class "Default")
      (node (ref "M2") (pin "12") (pinfunction "S1A_12") (pintype "power_in"))
      (node (ref "R26") (pin "1") (pinfunction "1_1") (pintype "passive"))
    )
    (net (code "48") (name "Net-(M2-S1B)") (class "Default")
      (node (ref "M2") (pin "1") (pinfunction "S1B_1") (pintype "power_in"))
      (node (ref "R26") (pin "2") (pinfunction "2_2") (pintype "passive"))
    )
    (net (code "49") (name "Net-(M2-S2A)") (class "Default")
      (node (ref "M2") (pin "14") (pinfunction "S2A_14") (pintype "passive"))
      (node (ref "R28") (pin "1") (pinfunction "1_1") (pintype "passive"))
    )
    (net (code "50") (name "Net-(M2-S2B)") (class "Default")
      (node (ref "M2") (pin "5") (pinfunction "S2B_5") (pintype "passive"))
      (node (ref "R28") (pin "2") (pinfunction "2_2") (pintype "passive"))
    )
    (net (code "51") (name "Net-(M2-S3A)") (class "Default")
      (node (ref "M2") (pin "15") (pinfunction "S3A_15") (pintype "passive"))
      (node (ref "R29") (pin "1") (pinfunction "1_1") (pintype "passive"))
    )
    (net (code "52") (name "Net-(M2-S3B)") (class "Default")
      (node (ref "M2") (pin "2") (pinfunction "S3B_2") (pintype "passive"))
      (node (ref "R29") (pin "2") (pinfunction "2_2") (pintype "passive"))
    )
    (net (code "53") (name "Net-(M2-S4A)") (class "Default")
      (node (ref "M2") (pin "11") (pinfunction "S4A_11") (pintype "passive"))
      (node (ref "R30") (pin "1") (pinfunction "1_1") (pintype "passive"))
    )
    (net (code "54") (name "Net-(M2-S4B)") (class "Default")
      (node (ref "M2") (pin "4") (pinfunction "S4B_4") (pintype "passive"))
      (node (ref "R30") (pin "2") (pinfunction "2_2") (pintype "passive"))
    )
    (net (code "55") (name "Net-(MIX1-IF)") (class "Default")
      (node (ref "C1") (pin "2") (pinfunction "2_2") (pintype "passive"))
      (node (ref "MIX1") (pin "5") (pinfunction "IF_5") (pintype "output"))
    )
    (net (code "56") (name "Net-(MIX1-LO)") (class "Default")
      (node (ref "MCX8") (pin "1") (pinfunction "1_1") (pintype "passive"))
      (node (ref "MIX1") (pin "2") (pinfunction "LO_2") (pintype "input"))
    )
    (net (code "57") (name "Net-(MIX1-RF)") (class "Default")
      (node (ref "MCX7") (pin "1") (pinfunction "1_1") (pintype "passive"))
      (node (ref "MIX1") (pin "7") (pinfunction "RF_7") (pintype "input"))
    )
    (net (code "58") (name "Net-(MIX2-IF)") (class "Default")
      (node (ref "C62") (pin "1") (pinfunction "1_1") (pintype "passive"))
      (node (ref "MIX2") (pin "5") (pinfunction "IF_5") (pintype "output"))
    )
    (net (code "59") (name "Net-(MIX2-LO)") (class "Default")
      (node (ref "MCX2") (pin "1") (pinfunction "1_1") (pintype "passive"))
      (node (ref "MIX2") (pin "2") (pinfunction "LO_2") (pintype "input"))
    )
    (net (code "60") (name "Net-(MIX2-RF)") (class "Default")
      (node (ref "MIX2") (pin "7") (pinfunction "RF_7") (pintype "input"))
      (node (ref "XL1") (pin "10") (pinfunction "Output_10") (pintype "output"))
    )
    (net (code "61") (name "Net-(OA1-+In)") (class "Default")
      (node (ref "C10") (pin "1") (pinfunction "1_1") (pintype "passive"))
      (node (ref "C15") (pin "1") (pinfunction "1_1") (pintype "passive"))
      (node (ref "OA1") (pin "3") (pinfunction "+In_3") (pintype "input"))
      (node (ref "R6") (pin "2") (pinfunction "2_2") (pintype "passive"))
    )
    (net (code "62") (name "Net-(OA1-Cc)") (class "Default")
      (node (ref "C25") (pin "1") (pinfunction "1_1") (pintype "passive"))
      (node (ref "OA1") (pin "5") (pinfunction "Cc_5") (pintype "passive"))
    )
    (net (code "63") (name "Net-(OA1-Disable)") (class "Default")
      (node (ref "OA1") (pin "8") (pinfunction "Disable_8") (pintype "passive"))
      (node (ref "R2") (pin "2") (pinfunction "2_2") (pintype "passive"))
    )
    (net (code "64") (name "Net-(OA1-Vout)") (class "Default")
      (node (ref "C16") (pin "1") (pinfunction "1_1") (pintype "passive"))
      (node (ref "C18") (pin "1") (pinfunction "1_1") (pintype "passive"))
      (node (ref "OA1") (pin "6") (pinfunction "Vout_6") (pintype "output"))
      (node (ref "R8") (pin "1") (pinfunction "1_1") (pintype "passive"))
    )
    (net (code "65") (name "Net-(OA2-+In)") (class "Default")
      (node (ref "C11") (pin "2") (pinfunction "2_2") (pintype "passive"))
      (node (ref "C16") (pin "2") (pinfunction "2_2") (pintype "passive"))
      (node (ref "OA2") (pin "3") (pinfunction "+In_3") (pintype "input"))
      (node (ref "R7") (pin "2") (pinfunction "2_2") (pintype "passive"))
    )
    (net (code "66") (name "Net-(OA2-Cc)") (class "Default")
      (node (ref "C24") (pin "2") (pinfunction "2_2") (pintype "passive"))
      (node (ref "OA2") (pin "5") (pinfunction "Cc_5") (pintype "passive"))
    )
    (net (code "67") (name "Net-(OA2-Disable)") (class "Default")
      (node (ref "OA2") (pin "8") (pinfunction "Disable_8") (pintype "passive"))
      (node (ref "R3") (pin "2") (pinfunction "2_2") (pintype "passive"))
    )
    (net (code "68") (name "Net-(OA2-Vout)") (class "Default")
      (node (ref "C13") (pin "1") (pinfunction "1_1") (pintype "passive"))
      (node (ref "C17") (pin "2") (pinfunction "2_2") (pintype "passive"))
      (node (ref "OA2") (pin "6") (pinfunction "Vout_6") (pintype "output"))
      (node (ref "R9") (pin "1") (pinfunction "1_1") (pintype "passive"))
    )
    (net (code "69") (name "Net-(OA3-+In)") (class "Default")
      (node (ref "C13") (pin "2") (pinfunction "2_2") (pintype "passive"))
      (node (ref "C9") (pin "2") (pinfunction "2_2") (pintype "passive"))
      (node (ref "OA3") (pin "3") (pinfunction "+In_3") (pintype "input"))
      (node (ref "R5") (pin "2") (pinfunction "2_2") (pintype "passive"))
    )
    (net (code "70") (name "Net-(OA3-+Vs)") (class "Default")
      (node (ref "C20") (pin "2") (pinfunction "2_2") (pintype "passive"))
      (node (ref "C21") (pin "1") (pinfunction "1_1") (pintype "passive"))
      (node (ref "FB4") (pin "1") (pinfunction "1_1") (pintype "passive"))
      (node (ref "OA3") (pin "7") (pinfunction "+Vs_7") (pintype "passive"))
      (node (ref "R17") (pin "2") (pinfunction "2_2") (pintype "passive"))
      (node (ref "R4") (pin "1") (pinfunction "1_1") (pintype "passive"))
    )
    (net (code "71") (name "Net-(OA3--In)") (class "Default")
      (node (ref "C8") (pin "1") (pinfunction "1_1") (pintype "passive"))
      (node (ref "OA3") (pin "2") (pinfunction "-In_2") (pintype "input"))
      (node (ref "R14") (pin "2") (pinfunction "2_2") (pintype "passive"))
      (node (ref "R31") (pin "1") (pinfunction "1_1") (pintype "passive"))
    )
    (net (code "72") (name "Net-(OA3-Cc)") (class "Default")
      (node (ref "C26") (pin "2") (pinfunction "2_2") (pintype "passive"))
      (node (ref "OA3") (pin "5") (pinfunction "Cc_5") (pintype "passive"))
    )
    (net (code "73") (name "Net-(OA3-Disable)") (class "Default")
      (node (ref "OA3") (pin "8") (pinfunction "Disable_8") (pintype "passive"))
      (node (ref "R4") (pin "2") (pinfunction "2_2") (pintype "passive"))
    )
    (net (code "74") (name "Net-(OA3-Feedback)") (class "Default")
      (node (ref "C8") (pin "2") (pinfunction "2_2") (pintype "passive"))
      (node (ref "OA3") (pin "1") (pinfunction "Feedback_1") (pintype "passive"))
      (node (ref "R31") (pin "2") (pinfunction "2_2") (pintype "passive"))
    )
    (net (code "75") (name "Net-(OA3-Vout)") (class "Default")
      (node (ref "C19") (pin "2") (pinfunction "2_2") (pintype "passive"))
      (node (ref "OA3") (pin "6") (pinfunction "Vout_6") (pintype "output"))
      (node (ref "R10") (pin "1") (pinfunction "1_1") (pintype "passive"))
      (node (ref "X3") (pin "1") (pinfunction "1_1") (pintype "passive"))
    )
    (net (code "76") (name "Net-(XL1-Input)") (class "Default")
      (node (ref "MCX1") (pin "1") (pinfunction "1_1") (pintype "passive"))
      (node (ref "XL1") (pin "3") (pinfunction "Input_3") (pintype "input"))
    )
    (net (code "77") (name "Net-(XL1-VD1)") (class "Default")
      (node (ref "C53") (pin "2") (pinfunction "2_2") (pintype "passive"))
      (node (ref "C54") (pin "2") (pinfunction "2_2") (pintype "passive"))
      (node (ref "C56") (pin "2") (pinfunction "2_2") (pintype "passive"))
      (node (ref "C57") (pin "2") (pinfunction "2_2") (pintype "passive"))
      (node (ref "C58") (pin "2") (pinfunction "2_2") (pintype "passive"))
      (node (ref "C59") (pin "2") (pinfunction "2_2") (pintype "passive"))
      (node (ref "C60") (pin "2") (pinfunction "2_2") (pintype "passive"))
      (node (ref "C61") (pin "2") (pinfunction "2_2") (pintype "passive"))
      (node (ref "FB9") (pin "1") (pinfunction "1_1") (pintype "passive"))
      (node (ref "XL1") (pin "13") (pinfunction "VD2_13") (pintype "passive"))
      (node (ref "XL1") (pin "14") (pinfunction "VG2_14") (pintype "passive"))
      (node (ref "XL1") (pin "15") (pinfunction "VD1_15") (pintype "passive"))
      (node (ref "XL1") (pin "16") (pinfunction "VG1_16") (pintype "passive"))
    )
    (net (code "78") (name "unconnected-(MCX1-GND-Pad2)") (class "Default")
      (node (ref "MCX1") (pin "2") (pinfunction "GND_2") (pintype "passive"))
    )
    (net (code "79") (name "unconnected-(MCX2-GND-Pad2)") (class "Default")
      (node (ref "MCX2") (pin "2") (pinfunction "GND_2") (pintype "passive"))
    )
    (net (code "80") (name "unconnected-(MCX7-GND-Pad2)") (class "Default")
      (node (ref "MCX7") (pin "2") (pinfunction "GND_2") (pintype "passive"))
    )
    (net (code "81") (name "unconnected-(MCX8-GND-Pad2)") (class "Default")
      (node (ref "MCX8") (pin "2") (pinfunction "GND_2") (pintype "passive"))
    )
  )
)
